# microSD-v2017.net
KiCad netlist of a schematic drawn in EAGLE
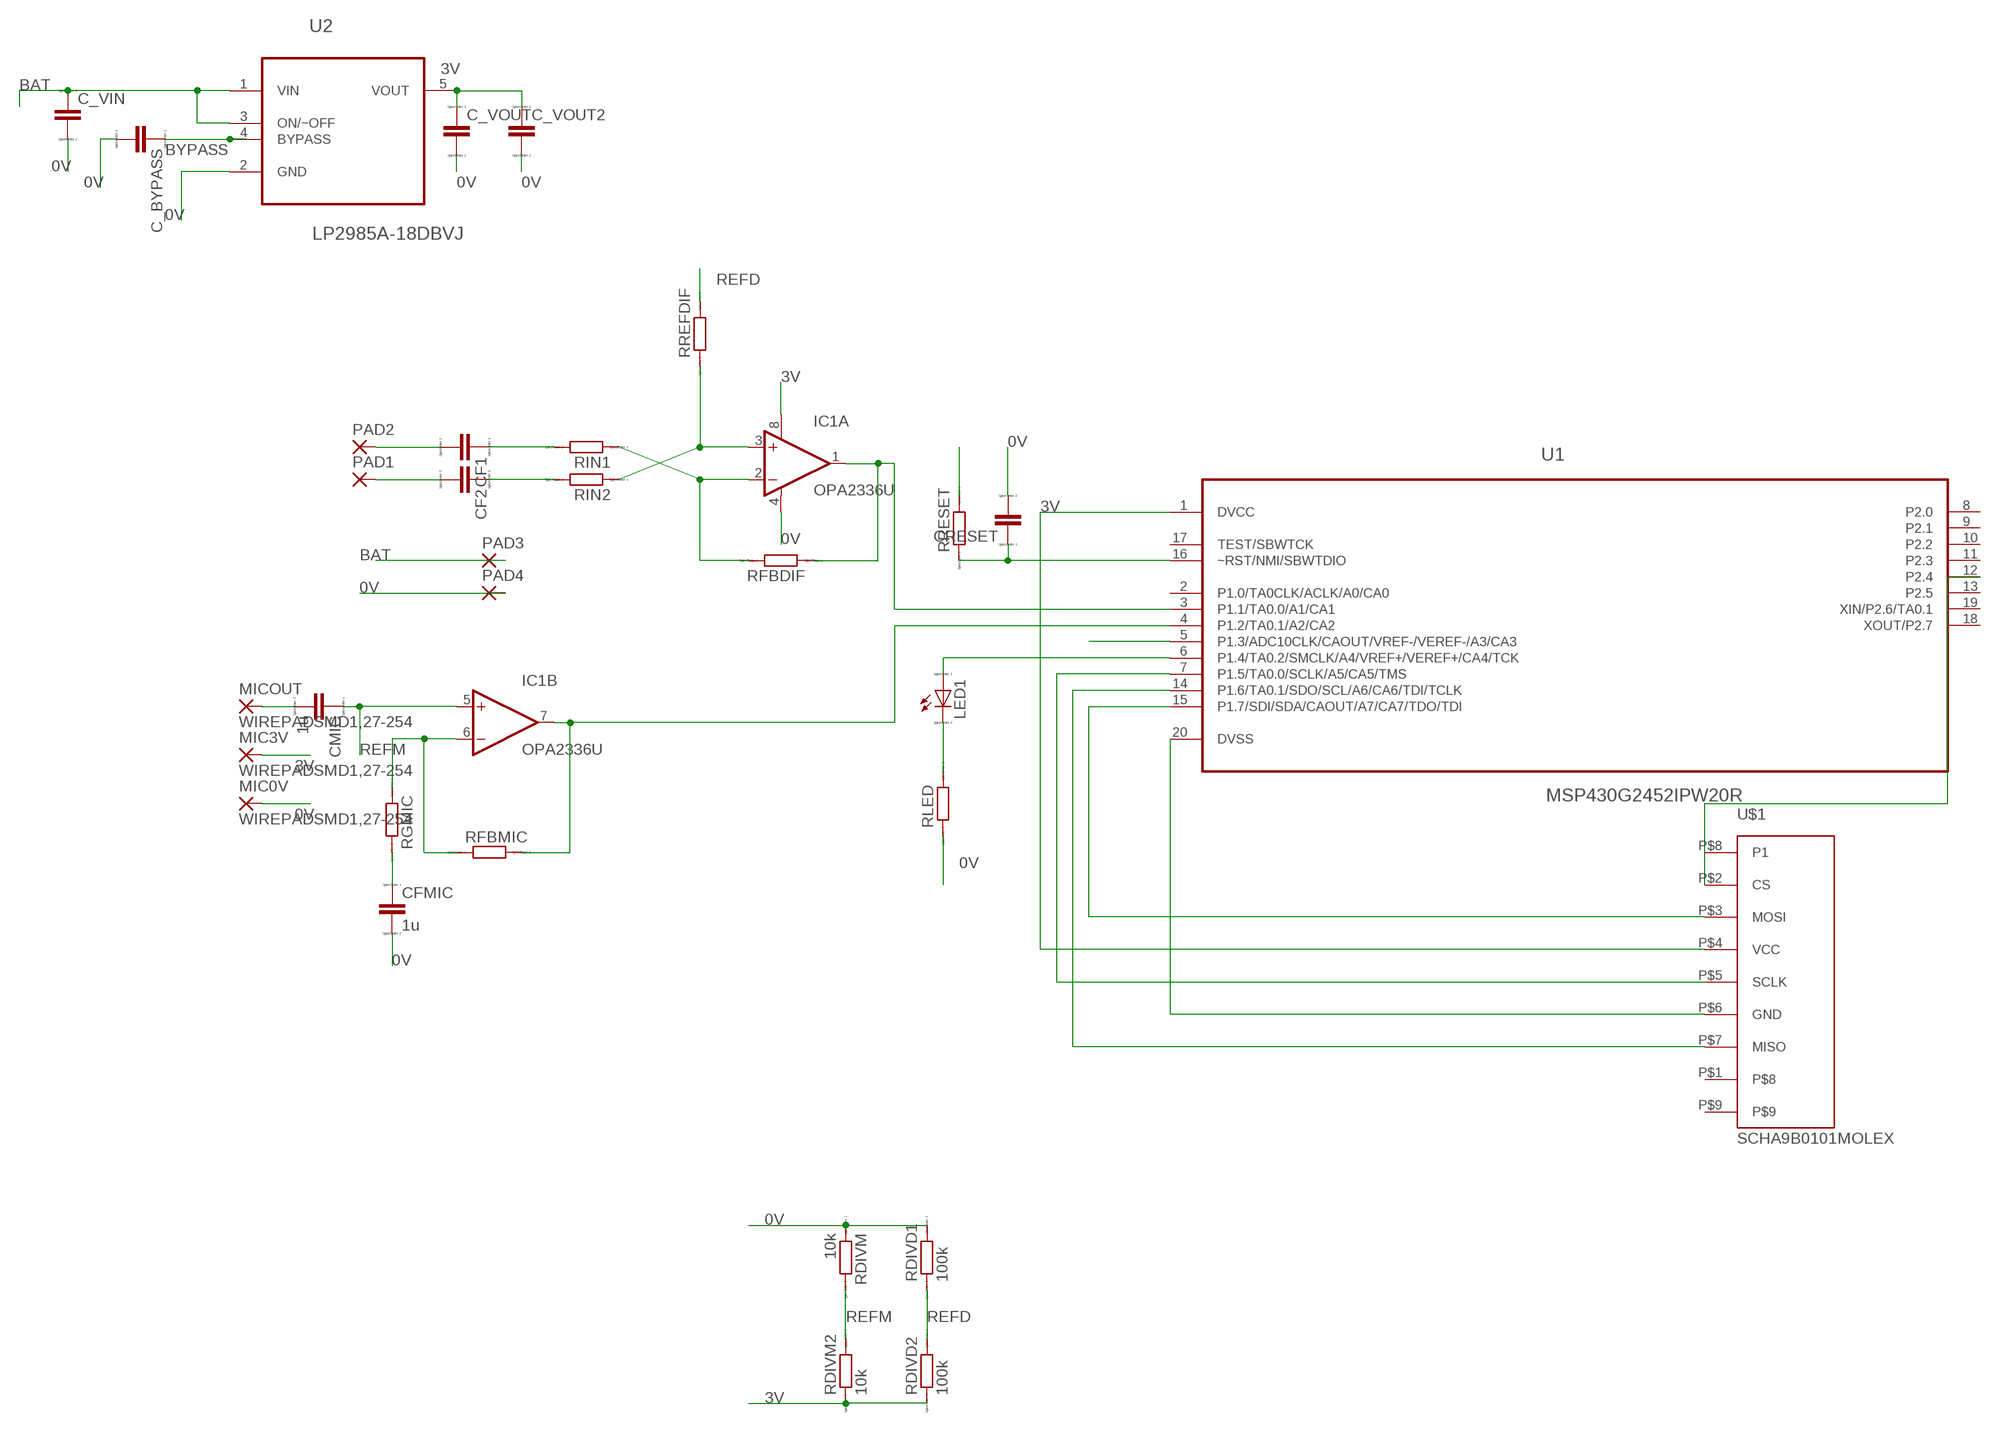
[diagram p0: schematic, sheet 1]

(export (version "E")
  (design (tool "Eeschema 10.0.6"))
  (components
    (comp (ref "CF1")
      (value "C")
      (footprint "eagle-import:C0805")
      (libsource (lib "eagle-import") (part "C"))
    )
    (comp (ref "CF2")
      (value "C")
      (footprint "eagle-import:C0805")
      (libsource (lib "eagle-import") (part "C"))
    )
    (comp (ref "CFMIC")
      (value "1u")
      (footprint "eagle-import:C0805")
      (libsource (lib "eagle-import") (part "C"))
    )
    (comp (ref "CMIC")
      (value "1u")
      (footprint "eagle-import:C0805")
      (libsource (lib "eagle-import") (part "C"))
    )
    (comp (ref "CRESET")
      (value "C")
      (footprint "eagle-import:C0805")
      (libsource (lib "eagle-import") (part "C"))
    )
    (comp (ref "C_BYPASS")
      (value "C")
      (footprint "eagle-import:C0805")
      (libsource (lib "eagle-import") (part "C"))
    )
    (comp (ref "C_VIN")
      (value "C")
      (footprint "eagle-import:C0805")
      (libsource (lib "eagle-import") (part "C"))
    )
    (comp (ref "C_VOUT")
      (value "C")
      (footprint "eagle-import:C0805")
      (libsource (lib "eagle-import") (part "C"))
    )
    (comp (ref "C_VOUT2")
      (value "C")
      (footprint "eagle-import:C0805")
      (libsource (lib "eagle-import") (part "C"))
    )
    (comp (ref "IC1")
      (value "OPA2336U")
      (footprint "eagle-import:SO08")
      (fields (field (name "MPN") "OPA2336UA"))
      (libsource (lib "eagle-import") (part "OPA2336U"))
    )
    (comp (ref "LED1")
      (value "LED_ESML0603")
      (footprint "eagle-import:LED_SML0603")
      (libsource (lib "eagle-import") (part "LED_ESML0603"))
    )
    (comp (ref "MIC0V")
      (value "WIREPADSMD1,27-254")
      (footprint "eagle-import:SMD1,27-2,54")
      (libsource (lib "eagle-import") (part "WIREPADSMD1,27-254"))
    )
    (comp (ref "MIC3V")
      (value "WIREPADSMD1,27-254")
      (footprint "eagle-import:SMD1,27-2,54")
      (libsource (lib "eagle-import") (part "WIREPADSMD1,27-254"))
    )
    (comp (ref "MICOUT")
      (value "WIREPADSMD1,27-254")
      (footprint "eagle-import:SMD1,27-2,54")
      (libsource (lib "eagle-import") (part "WIREPADSMD1,27-254"))
    )
    (comp (ref "PAD1")
      (value "SMD2")
      (footprint "eagle-import:SMD1,27-2,54")
      (libsource (lib "eagle-import") (part "SMD2"))
    )
    (comp (ref "PAD2")
      (value "SMD2")
      (footprint "eagle-import:SMD1,27-2,54")
      (libsource (lib "eagle-import") (part "SMD2"))
    )
    (comp (ref "PAD3")
      (value "SMD2")
      (footprint "eagle-import:SMD1,27-2,54")
      (libsource (lib "eagle-import") (part "SMD2"))
    )
    (comp (ref "PAD4")
      (value "SMD2")
      (footprint "eagle-import:SMD1,27-2,54")
      (libsource (lib "eagle-import") (part "SMD2"))
    )
    (comp (ref "RDIVD1")
      (value "100k")
      (footprint "eagle-import:R0805")
      (libsource (lib "eagle-import") (part "R"))
    )
    (comp (ref "RDIVD2")
      (value "100k")
      (footprint "eagle-import:R0805")
      (libsource (lib "eagle-import") (part "R"))
    )
    (comp (ref "RDIVM")
      (value "10k")
      (footprint "eagle-import:R0805")
      (libsource (lib "eagle-import") (part "R"))
    )
    (comp (ref "RDIVM2")
      (value "10k")
      (footprint "eagle-import:R0805")
      (libsource (lib "eagle-import") (part "R"))
    )
    (comp (ref "RFBDIF")
      (value "R")
      (footprint "eagle-import:R0805")
      (libsource (lib "eagle-import") (part "R"))
    )
    (comp (ref "RFBMIC")
      (value "R")
      (footprint "eagle-import:R0805")
      (libsource (lib "eagle-import") (part "R"))
    )
    (comp (ref "RGMIC")
      (value "R")
      (footprint "eagle-import:R0805")
      (libsource (lib "eagle-import") (part "R"))
    )
    (comp (ref "RIN1")
      (value "R")
      (footprint "eagle-import:R0805")
      (libsource (lib "eagle-import") (part "R"))
    )
    (comp (ref "RIN2")
      (value "R")
      (footprint "eagle-import:R0805")
      (libsource (lib "eagle-import") (part "R"))
    )
    (comp (ref "RLED")
      (value "RR0603")
      (footprint "eagle-import:R0603")
      (libsource (lib "eagle-import") (part "RR0603"))
    )
    (comp (ref "RREFDIF")
      (value "R")
      (footprint "eagle-import:R0805")
      (libsource (lib "eagle-import") (part "R"))
    )
    (comp (ref "RRESET")
      (value "R")
      (footprint "eagle-import:R0805")
      (libsource (lib "eagle-import") (part "R"))
    )
    (comp (ref "U$1")
      (value "SCHA9B0101MOLEX")
      (footprint "eagle-import:SMD-MOLEX")
      (libsource (lib "eagle-import") (part "SCHA9B0101MOLEX"))
    )
    (comp (ref "U1")
      (value "MSP430G2452IPW20R")
      (footprint "eagle-import:SOP65P640X120-20N")
      (libsource (lib "eagle-import") (part "MSP430G2452IPW20R"))
    )
    (comp (ref "U2")
      (value "LP2985A-18DBVJ")
      (footprint "eagle-import:SOT95P280X145-5N")
      (libsource (lib "eagle-import") (part "LP2985A-18DBVJ"))
    )
  )
  (nets
    (net (code "1") (name "/0V") (class "Default")
      (node (ref "CFMIC") (pin "2") (pinfunction "2_2") (pintype "passive"))
      (node (ref "CRESET") (pin "2") (pinfunction "2_2") (pintype "passive"))
      (node (ref "C_BYPASS") (pin "2") (pinfunction "2_2") (pintype "passive"))
      (node (ref "C_VIN") (pin "2") (pinfunction "2_2") (pintype "passive"))
      (node (ref "C_VOUT") (pin "2") (pinfunction "2_2") (pintype "passive"))
      (node (ref "C_VOUT2") (pin "2") (pinfunction "2_2") (pintype "passive"))
      (node (ref "IC1") (pin "4") (pinfunction "V-_4") (pintype "power_in"))
      (node (ref "MIC0V") (pin "1") (pinfunction "P_1") (pintype "passive"))
      (node (ref "PAD4") (pin "1") (pinfunction "P_1") (pintype "passive"))
      (node (ref "RDIVD1") (pin "2") (pinfunction "2_2") (pintype "passive"))
      (node (ref "RDIVM") (pin "1") (pinfunction "1_1") (pintype "passive"))
      (node (ref "RLED") (pin "1") (pinfunction "1_1") (pintype "passive"))
      (node (ref "U$1") (pin "P$6") (pinfunction "GND_P$6") (pintype "bidirectional"))
      (node (ref "U1") (pin "20") (pinfunction "DVSS_20") (pintype "passive"))
      (node (ref "U2") (pin "2") (pinfunction "GND_2") (pintype "passive"))
    )
    (net (code "2") (name "/3V") (class "Default")
      (node (ref "C_VOUT") (pin "1") (pinfunction "1_1") (pintype "passive"))
      (node (ref "C_VOUT2") (pin "1") (pinfunction "1_1") (pintype "passive"))
      (node (ref "IC1") (pin "8") (pinfunction "V+_8") (pintype "power_in"))
      (node (ref "MIC3V") (pin "1") (pinfunction "P_1") (pintype "passive"))
      (node (ref "RDIVD2") (pin "1") (pinfunction "1_1") (pintype "passive"))
      (node (ref "RDIVM2") (pin "1") (pinfunction "1_1") (pintype "passive"))
      (node (ref "RRESET") (pin "2") (pinfunction "2_2") (pintype "passive"))
      (node (ref "U$1") (pin "P$4") (pinfunction "VCC_P$4") (pintype "bidirectional"))
      (node (ref "U1") (pin "1") (pinfunction "DVCC_1") (pintype "power_in"))
      (node (ref "U2") (pin "5") (pinfunction "VOUT_5") (pintype "output"))
    )
    (net (code "3") (name "/BAT") (class "Default")
      (node (ref "C_VIN") (pin "1") (pinfunction "1_1") (pintype "passive"))
      (node (ref "PAD3") (pin "1") (pinfunction "P_1") (pintype "passive"))
      (node (ref "U2") (pin "1") (pinfunction "VIN_1") (pintype "input"))
      (node (ref "U2") (pin "3") (pinfunction "ON/~{OFF}_3") (pintype "input"))
    )
    (net (code "4") (name "/BYPASS") (class "Default")
      (node (ref "C_BYPASS") (pin "1") (pinfunction "1_1") (pintype "passive"))
      (node (ref "U2") (pin "4") (pinfunction "BYPASS_4") (pintype "input"))
    )
    (net (code "5") (name "/REFD") (class "Default")
      (node (ref "RDIVD1") (pin "1") (pinfunction "1_1") (pintype "passive"))
      (node (ref "RDIVD2") (pin "2") (pinfunction "2_2") (pintype "passive"))
      (node (ref "RREFDIF") (pin "2") (pinfunction "2_2") (pintype "passive"))
    )
    (net (code "6") (name "/REFM") (class "Default")
      (node (ref "CMIC") (pin "1") (pinfunction "1_1") (pintype "passive"))
      (node (ref "IC1") (pin "5") (pinfunction "+IN_5") (pintype "input"))
      (node (ref "RDIVM") (pin "2") (pinfunction "2_2") (pintype "passive"))
      (node (ref "RDIVM2") (pin "2") (pinfunction "2_2") (pintype "passive"))
    )
    (net (code "7") (name "Net-(CF1-Pad1)") (class "Default")
      (node (ref "CF1") (pin "1") (pinfunction "1_1") (pintype "passive"))
      (node (ref "RIN1") (pin "2") (pinfunction "2_2") (pintype "passive"))
    )
    (net (code "8") (name "Net-(CF2-Pad1)") (class "Default")
      (node (ref "CF2") (pin "1") (pinfunction "1_1") (pintype "passive"))
      (node (ref "RIN2") (pin "2") (pinfunction "2_2") (pintype "passive"))
    )
    (net (code "9") (name "Net-(CFMIC-Pad1)") (class "Default")
      (node (ref "CFMIC") (pin "1") (pinfunction "1_1") (pintype "passive"))
      (node (ref "RGMIC") (pin "2") (pinfunction "2_2") (pintype "passive"))
    )
    (net (code "10") (name "Net-(IC1A-+IN)") (class "Default")
      (node (ref "IC1") (pin "3") (pinfunction "+IN_3") (pintype "input"))
      (node (ref "RIN2") (pin "1") (pinfunction "1_1") (pintype "passive"))
      (node (ref "RREFDIF") (pin "1") (pinfunction "1_1") (pintype "passive"))
    )
    (net (code "11") (name "Net-(IC1A--IN)") (class "Default")
      (node (ref "IC1") (pin "2") (pinfunction "-IN_2") (pintype "input"))
      (node (ref "RFBDIF") (pin "2") (pinfunction "2_2") (pintype "passive"))
      (node (ref "RIN1") (pin "1") (pinfunction "1_1") (pintype "passive"))
    )
    (net (code "12") (name "Net-(IC1A-OUT)") (class "Default")
      (node (ref "IC1") (pin "1") (pinfunction "OUT_1") (pintype "output"))
      (node (ref "RFBDIF") (pin "1") (pinfunction "1_1") (pintype "passive"))
      (node (ref "U1") (pin "3") (pinfunction "P1.1/TA0.0/A1/CA1_3") (pintype "bidirectional"))
    )
    (net (code "13") (name "Net-(IC1B--IN)") (class "Default")
      (node (ref "IC1") (pin "6") (pinfunction "-IN_6") (pintype "input"))
      (node (ref "RFBMIC") (pin "1") (pinfunction "1_1") (pintype "passive"))
      (node (ref "RGMIC") (pin "1") (pinfunction "1_1") (pintype "passive"))
    )
    (net (code "14") (name "Net-(IC1B-OUT)") (class "Default")
      (node (ref "IC1") (pin "7") (pinfunction "OUT_7") (pintype "output"))
      (node (ref "RFBMIC") (pin "2") (pinfunction "2_2") (pintype "passive"))
      (node (ref "U1") (pin "4") (pinfunction "P1.2/TA0.1/A2/CA2_4") (pintype "bidirectional"))
    )
    (net (code "15") (name "Net-(LED1-PadC)") (class "Default")
      (node (ref "LED1") (pin "C") (pinfunction "C_C") (pintype "passive"))
      (node (ref "RLED") (pin "2") (pinfunction "2_2") (pintype "passive"))
    )
    (net (code "16") (name "Net-(MICOUT-P)") (class "Default")
      (node (ref "CMIC") (pin "2") (pinfunction "2_2") (pintype "passive"))
      (node (ref "MICOUT") (pin "1") (pinfunction "P_1") (pintype "passive"))
    )
    (net (code "17") (name "Net-(PAD1-P)") (class "Default")
      (node (ref "CF2") (pin "2") (pinfunction "2_2") (pintype "passive"))
      (node (ref "PAD1") (pin "1") (pinfunction "P_1") (pintype "passive"))
    )
    (net (code "18") (name "Net-(PAD2-P)") (class "Default")
      (node (ref "CF1") (pin "2") (pinfunction "2_2") (pintype "passive"))
      (node (ref "PAD2") (pin "1") (pinfunction "P_1") (pintype "passive"))
    )
    (net (code "19") (name "Net-(U$1-CS)") (class "Default")
      (node (ref "U$1") (pin "P$2") (pinfunction "CS_P$2") (pintype "bidirectional"))
      (node (ref "U1") (pin "12") (pinfunction "P2.4_12") (pintype "bidirectional"))
    )
    (net (code "20") (name "Net-(U$1-MISO)") (class "Default")
      (node (ref "U$1") (pin "P$7") (pinfunction "MISO_P$7") (pintype "bidirectional"))
      (node (ref "U1") (pin "14") (pinfunction "P1.6/TA0.1/SDO/SCL/A6/CA6/TDI/TCLK_14") (pintype "bidirectional"))
    )
    (net (code "21") (name "Net-(U$1-MOSI)") (class "Default")
      (node (ref "U$1") (pin "P$3") (pinfunction "MOSI_P$3") (pintype "bidirectional"))
      (node (ref "U1") (pin "15") (pinfunction "P1.7/SDI/SDA/CAOUT/A7/CA7/TDO/TDI_15") (pintype "bidirectional"))
    )
    (net (code "22") (name "Net-(U$1-SCLK)") (class "Default")
      (node (ref "U$1") (pin "P$5") (pinfunction "SCLK_P$5") (pintype "bidirectional"))
      (node (ref "U1") (pin "7") (pinfunction "P1.5/TA0.0/SCLK/A5/CA5/TMS_7") (pintype "bidirectional"))
    )
    (net (code "23") (name "Net-(U1-P1.4{slash}TA0.2{slash}SMCLK{slash}A4{slash}VREF+{slash}VEREF+{slash}CA4{slash}TCK)") (class "Default")
      (node (ref "LED1") (pin "A") (pinfunction "A_A") (pintype "passive"))
      (node (ref "U1") (pin "6") (pinfunction "P1.4/TA0.2/SMCLK/A4/VREF+/VEREF+/CA4/TCK_6") (pintype "bidirectional"))
    )
    (net (code "24") (name "Net-(U1-~{RST{slash}NMI{slash}SBWTDIO})") (class "Default")
      (node (ref "CRESET") (pin "1") (pinfunction "1_1") (pintype "passive"))
      (node (ref "RRESET") (pin "1") (pinfunction "1_1") (pintype "passive"))
      (node (ref "U1") (pin "16") (pinfunction "~{RST/NMI/SBWTDIO}_16") (pintype "input"))
    )
    (net (code "25") (name "unconnected-(U$1-P$8-PadP$1)") (class "Default")
      (node (ref "U$1") (pin "P$1") (pinfunction "P$8_P$1") (pintype "bidirectional"))
    )
    (net (code "26") (name "unconnected-(U$1-P1-PadP$8)") (class "Default")
      (node (ref "U$1") (pin "P$8") (pinfunction "P1_P$8") (pintype "bidirectional"))
    )
    (net (code "27") (name "unconnected-(U$1-PadP$9)") (class "Default")
      (node (ref "U$1") (pin "P$9") (pinfunction "P$9_P$9") (pintype "bidirectional"))
    )
    (net (code "28") (name "unconnected-(U1-P1.0{slash}TA0CLK{slash}ACLK{slash}A0{slash}CA0-Pad2)") (class "Default")
      (node (ref "U1") (pin "2") (pinfunction "P1.0/TA0CLK/ACLK/A0/CA0_2") (pintype "bidirectional"))
    )
    (net (code "29") (name "unconnected-(U1-P1.3{slash}ADC10CLK{slash}CAOUT{slash}VREF-{slash}VEREF-{slash}A3{slash}CA3-Pad5)") (class "Default")
      (node (ref "U1") (pin "5") (pinfunction "P1.3/ADC10CLK/CAOUT/VREF-/VEREF-/A3/CA3_5") (pintype "bidirectional"))
    )
    (net (code "30") (name "unconnected-(U1-P2.0-Pad8)") (class "Default")
      (node (ref "U1") (pin "8") (pinfunction "P2.0_8") (pintype "bidirectional"))
    )
    (net (code "31") (name "unconnected-(U1-P2.1-Pad9)") (class "Default")
      (node (ref "U1") (pin "9") (pinfunction "P2.1_9") (pintype "bidirectional"))
    )
    (net (code "32") (name "unconnected-(U1-P2.2-Pad10)") (class "Default")
      (node (ref "U1") (pin "10") (pinfunction "P2.2_10") (pintype "bidirectional"))
    )
    (net (code "33") (name "unconnected-(U1-P2.3-Pad11)") (class "Default")
      (node (ref "U1") (pin "11") (pinfunction "P2.3_11") (pintype "bidirectional"))
    )
    (net (code "34") (name "unconnected-(U1-P2.5-Pad13)") (class "Default")
      (node (ref "U1") (pin "13") (pinfunction "P2.5_13") (pintype "bidirectional"))
    )
    (net (code "35") (name "unconnected-(U1-TEST{slash}SBWTCK-Pad17)") (class "Default")
      (node (ref "U1") (pin "17") (pinfunction "TEST/SBWTCK_17") (pintype "input"))
    )
    (net (code "36") (name "unconnected-(U1-XIN{slash}P2.6{slash}TA0.1-Pad19)") (class "Default")
      (node (ref "U1") (pin "19") (pinfunction "XIN/P2.6/TA0.1_19") (pintype "bidirectional"))
    )
    (net (code "37") (name "unconnected-(U1-XOUT{slash}P2.7-Pad18)") (class "Default")
      (node (ref "U1") (pin "18") (pinfunction "XOUT/P2.7_18") (pintype "bidirectional"))
    )
  )
)
